# led_matrix_board.net
KiCad netlist of a schematic drawn in Altium Designer
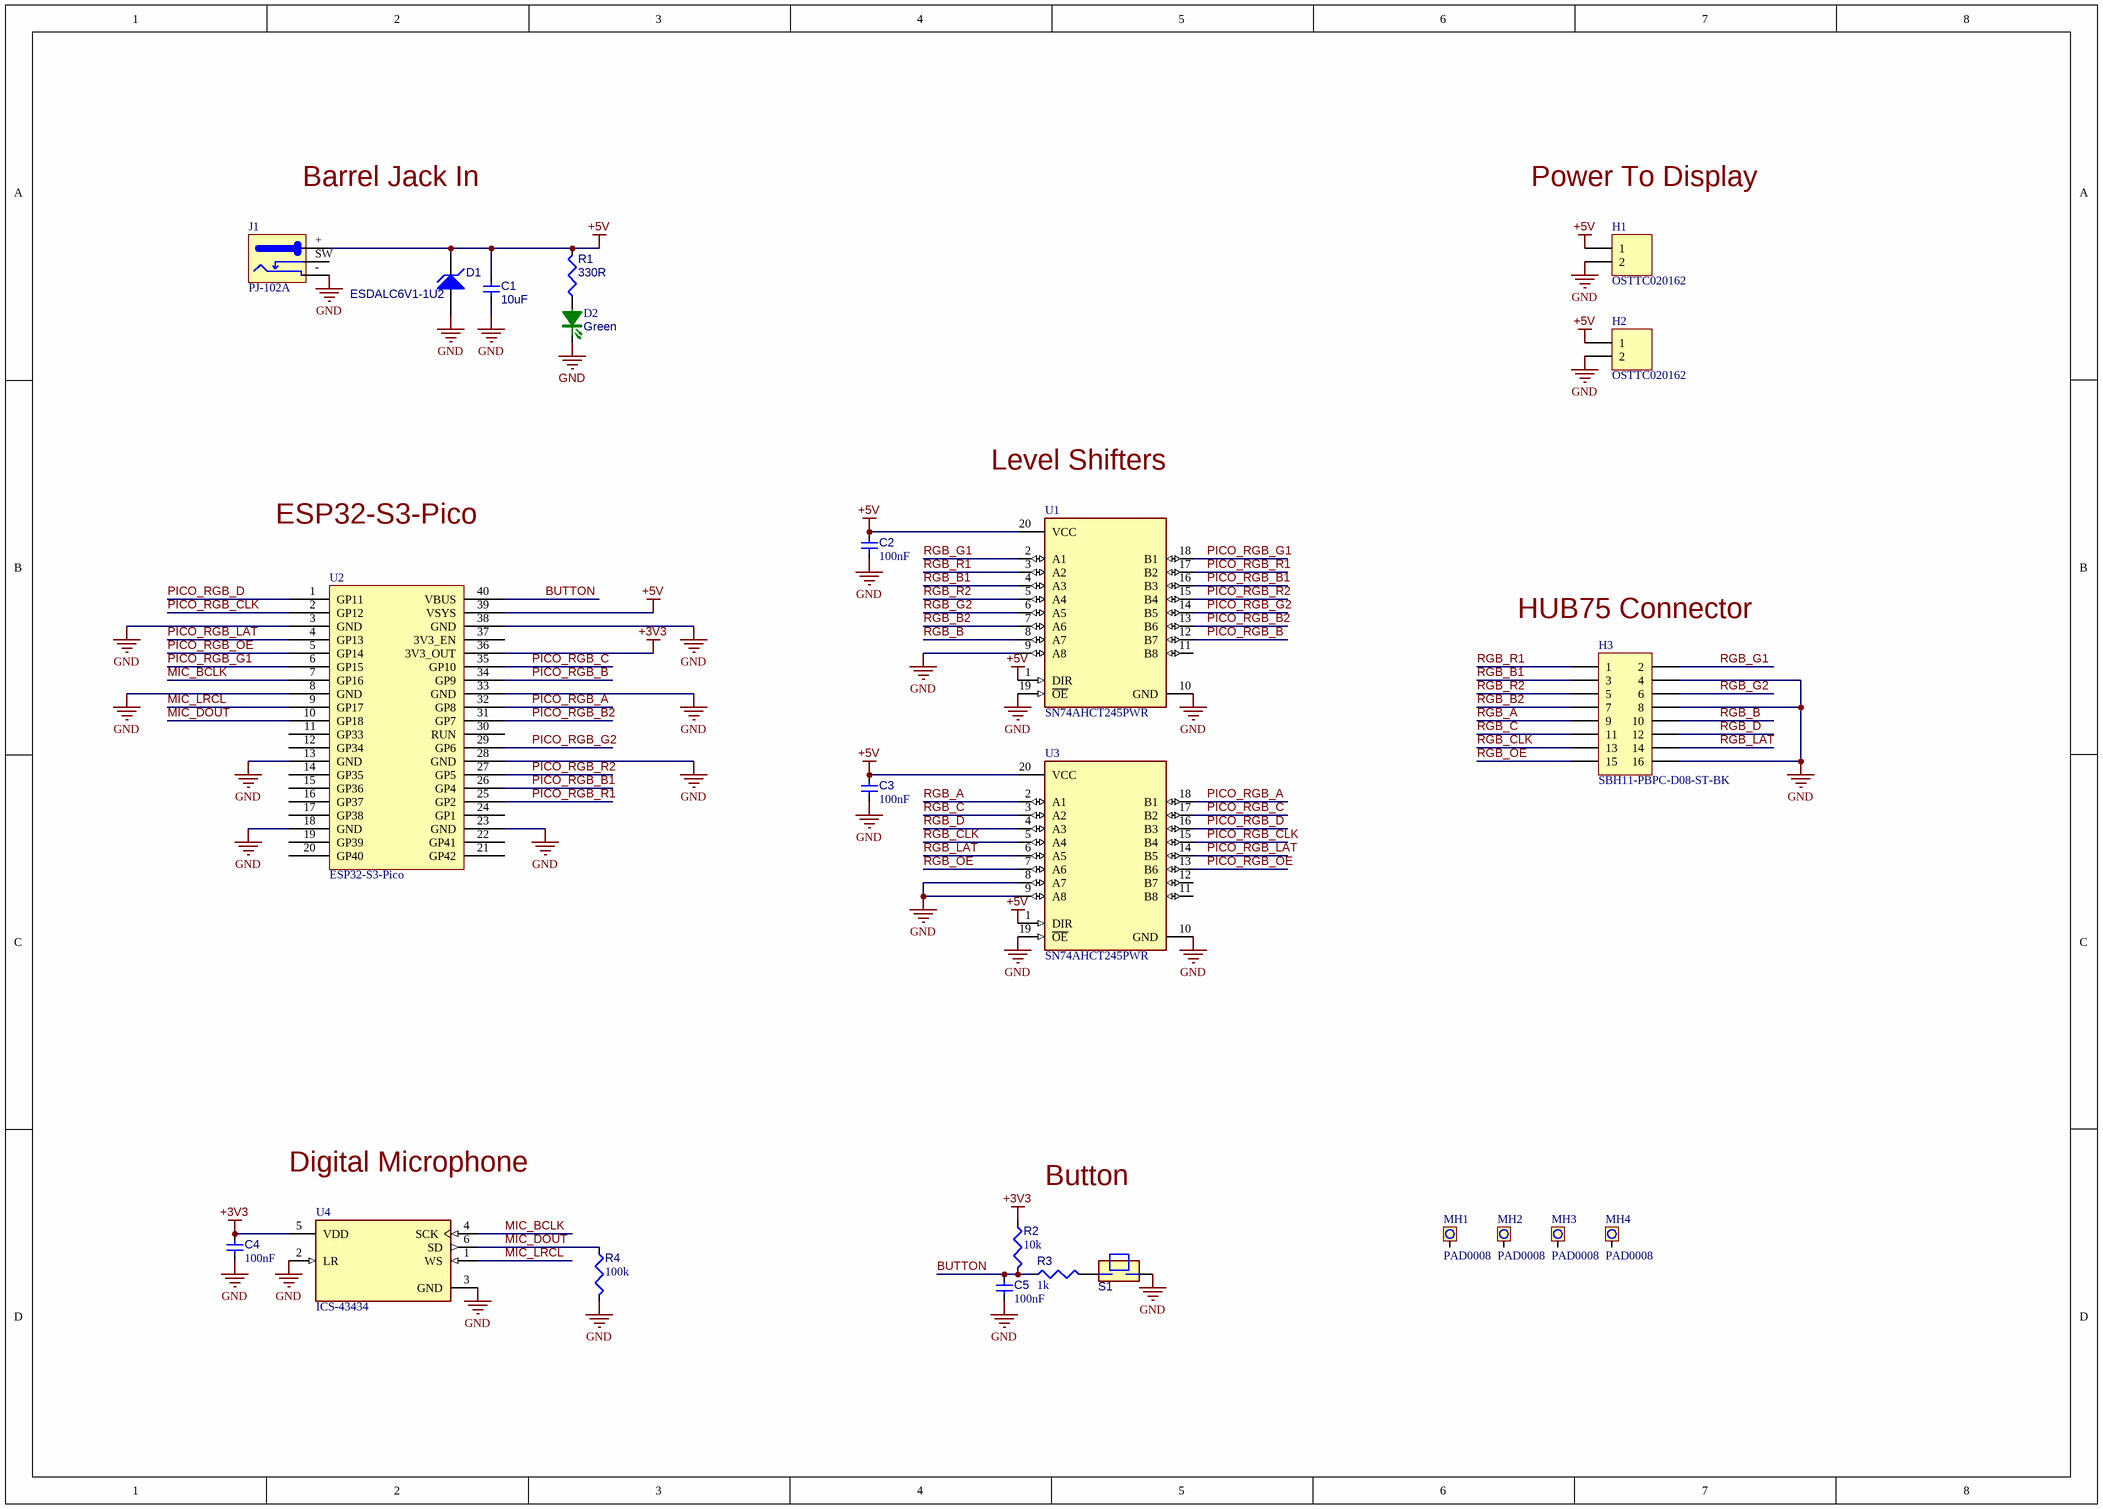
[diagram p0: led_matrix_board.SchDoc]

(export (version "E")
  (design (tool "Eeschema 10.0.6"))
  (components
    (comp (ref "C1")
      (value "10uF")
      (footprint "0603_cap_rnd")
      (description "CAP CER 10UF 25V ±20% X5R 0603")
      (fields (field (name "TOLERANCE") "20%") (field (name "VOLTAGE") "25V"))
      (libsource (lib "Morse Micro Pty Limited") (part "CAP"))
    )
    (comp (ref "C2")
      (value "100nF")
      (footprint "0603_cap")
      (description "CAP CER 100NF 10V ±10% X7R 0603")
      (fields (field (name "TOLERANCE") "10%") (field (name "VOLTAGE") "10V"))
      (libsource (lib "Morse Micro Pty Limited") (part "CAP"))
    )
    (comp (ref "C3")
      (value "100nF")
      (footprint "0603_cap")
      (description "CAP CER 100NF 10V ±10% X7R 0603")
      (fields (field (name "TOLERANCE") "10%") (field (name "VOLTAGE") "10V"))
      (libsource (lib "Morse Micro Pty Limited") (part "CAP"))
    )
    (comp (ref "C4")
      (value "100nF")
      (footprint "0603_cap")
      (description "CAP CER 100NF 10V ±10% X7R 0603")
      (fields (field (name "TOLERANCE") "10%") (field (name "VOLTAGE") "10V"))
      (libsource (lib "Morse Micro Pty Limited") (part "CAP"))
    )
    (comp (ref "C5")
      (value "100nF")
      (footprint "0603_cap")
      (description "CAP CER 100NF 10V ±10% X7R 0603")
      (fields (field (name "TOLERANCE") "10%") (field (name "VOLTAGE") "10V"))
      (libsource (lib "Morse Micro Pty Limited") (part "CAP"))
    )
    (comp (ref "D1")
      (value "ESDALC6V1-1U2")
      (footprint "0201_DIODE")
      (description "TVS DIODE 3VWM ST020")
      (fields (field (name "VOLTAGE") "3V") (field (name "POWER") "20W"))
      (libsource (lib "Morse Micro Pty Limited") (part "DIODE_ZENER"))
    )
    (comp (ref "D2")
      (value "Green")
      (footprint "LED_0402_GREEN")
      (description "LED GREEN 0402 SMD")
      (fields (field (name "VOLTAGE") "2.0V") (field (name "Comment") "XZVGR68W-3"))
      (libsource (lib "Morse Micro Pty Limited") (part "LED_G"))
    )
    (comp (ref "H1")
      (value "OSTTC020162")
      (footprint "SCREW_TERM_2WAY_5MM")
      (description "CONN TERM BLOCK 5MM 2POS")
      (libsource (lib "Morse Micro Pty Limited") (part "HDR_1X2"))
    )
    (comp (ref "H2")
      (value "OSTTC020162")
      (footprint "SCREW_TERM_2WAY_5MM")
      (description "CONN TERM BLOCK 5MM 2POS")
      (libsource (lib "Morse Micro Pty Limited") (part "HDR_1X2"))
    )
    (comp (ref "H3")
      (value "SBH11-PBPC-D08-ST-BK")
      (footprint "FP-SBH11-PBPC-D08-ST-BK-MFG")
      (description "Conn Shrouded Header (4 Sides) HDR 16 POS 2.54mm Solder ST Top Entry Thru-Hole")
      (libsource (lib "Morse Micro Pty Limited") (part "HDR_2X8"))
    )
    (comp (ref "J1")
      (value "PJ-102A")
      (footprint "PJ-102A")
      (description "Conn Power Jack 2.1mm PCB Mount Thru-Hole")
      (libsource (lib "Morse Micro Pty Limited") (part "2_1MM POWER"))
    )
    (comp (ref "MH1")
      (value "PAD0008")
      (footprint "MH_600_320_NPTH")
      (description "MH 6.00MM DIA 3.2MM HOLE NPTH")
      (libsource (lib "Morse Micro Pty Limited") (part "MH_600_320_NPTH"))
    )
    (comp (ref "MH2")
      (value "PAD0008")
      (footprint "MH_600_320_NPTH")
      (description "MH 6.00MM DIA 3.2MM HOLE NPTH")
      (libsource (lib "Morse Micro Pty Limited") (part "MH_600_320_NPTH"))
    )
    (comp (ref "MH3")
      (value "PAD0008")
      (footprint "MH_600_320_NPTH")
      (description "MH 6.00MM DIA 3.2MM HOLE NPTH")
      (libsource (lib "Morse Micro Pty Limited") (part "MH_600_320_NPTH"))
    )
    (comp (ref "MH4")
      (value "PAD0008")
      (footprint "MH_600_320_NPTH")
      (description "MH 6.00MM DIA 3.2MM HOLE NPTH")
      (libsource (lib "Morse Micro Pty Limited") (part "MH_600_320_NPTH"))
    )
    (comp (ref "R1")
      (value "330R")
      (footprint "0402_res")
      (description "RES SMD 330R OHM ±1% 1/16W 0402")
      (fields (field (name "POWER") "1/16W") (field (name "TOLERANCE") "1%"))
      (libsource (lib "Morse Micro Pty Limited") (part "RES"))
    )
    (comp (ref "R2")
      (value "10k")
      (footprint "0603_res")
      (description "RES SMD 10K OHM ±1% 1/10W 0603")
      (fields (field (name "POWER") "1/10W") (field (name "TOLERANCE") "1%"))
      (libsource (lib "Morse Micro Pty Limited") (part "RES"))
    )
    (comp (ref "R3")
      (value "1k")
      (footprint "0603_res")
      (description "RES SMD 1K OHM ±0 .1% 1/10W 0603")
      (fields (field (name "TOLERANCE") "0 .1%") (field (name "POWER") "1/10W"))
      (libsource (lib "Morse Micro Pty Limited") (part "RES"))
    )
    (comp (ref "R4")
      (value "100k")
      (footprint "0603_res")
      (description "RES SMD 100K OHM ±1% 1/10W 0603")
      (fields (field (name "POWER") "1/10W") (field (name "TOLERANCE") "1%"))
      (libsource (lib "Morse Micro Pty Limited") (part "RES"))
    )
    (comp (ref "S1")
      (value "EVQ-PF206K")
      (footprint "EVQ-PF206K")
      (description "SW, Tactile 15V@20mA, EVQ-PF, Through Hole, R/A, 7.5x7.1x5.85mm")
      (libsource (lib "Morse Micro Pty Limited") (part "SW_PB"))
    )
    (comp (ref "U1")
      (value "SN74AHCT245PWR")
      (footprint "FP-PW0020A-IPC_A")
      (description "8mA 8 4.5V~5.5V 8mA 1 TSSOP-20 Buffer/Driver/Transceiver ROHS")
      (libsource (lib "Morse Micro Pty Limited") (part "f8b0c07ade4f6b8d62f3b9458d8db27"))
    )
    (comp (ref "U2")
      (value "ESP32-S3-Pico")
      (footprint "ESP32-S3-Pico")
      (description "ESP32-S3-Pico Module.")
      (libsource (lib "Morse Micro Pty Limited") (part "ESP32-S3-Pico"))
    )
    (comp (ref "U3")
      (value "SN74AHCT245PWR")
      (footprint "FP-PW0020A-IPC_A")
      (description "8mA 8 4.5V~5.5V 8mA 1 TSSOP-20 Buffer/Driver/Transceiver ROHS")
      (libsource (lib "Morse Micro Pty Limited") (part "f8b0c07ade4f6b8d62f3b9458d8db27"))
    )
    (comp (ref "U4")
      (value "ICS-43434")
      (footprint "FP-ICS-43434-MFG")
      (description "Mic Omni-Directional -26dB 3.63V Rectangular Solder Pad T/R")
      (libsource (lib "Morse Micro Pty Limited") (part "ae05e933d23a1a1b08b70095a55dc98"))
    )
  )
  (nets
    (net (code "1") (name "+3V3") (class "Default")
      (node (ref "C4") (pin "1") (pinfunction "1_1") (pintype "passive"))
      (node (ref "R2") (pin "1") (pinfunction "1_1") (pintype "passive"))
      (node (ref "U2") (pin "36") (pinfunction "3V3_OUT_36") (pintype "passive"))
      (node (ref "U4") (pin "5") (pinfunction "VDD_5") (pintype "power_in"))
    )
    (net (code "2") (name "+5V") (class "Default")
      (node (ref "C1") (pin "1") (pinfunction "1_1") (pintype "passive"))
      (node (ref "C2") (pin "1") (pinfunction "1_1") (pintype "passive"))
      (node (ref "C3") (pin "1") (pinfunction "1_1") (pintype "passive"))
      (node (ref "D1") (pin "K") (pinfunction "K_K") (pintype "passive"))
      (node (ref "H1") (pin "1") (pinfunction "1_1") (pintype "passive"))
      (node (ref "H2") (pin "1") (pinfunction "1_1") (pintype "passive"))
      (node (ref "J1") (pin "+") (pinfunction "+_+") (pintype "passive"))
      (node (ref "R1") (pin "2") (pinfunction "2_2") (pintype "passive"))
      (node (ref "U1") (pin "1") (pinfunction "DIR_1") (pintype "input"))
      (node (ref "U1") (pin "20") (pinfunction "VCC_20") (pintype "power_in"))
      (node (ref "U2") (pin "39") (pinfunction "VSYS_39") (pintype "passive"))
      (node (ref "U3") (pin "1") (pinfunction "DIR_1") (pintype "input"))
      (node (ref "U3") (pin "20") (pinfunction "VCC_20") (pintype "power_in"))
    )
    (net (code "3") (name "/BUTTON") (class "Default")
      (node (ref "C5") (pin "1") (pinfunction "1_1") (pintype "passive"))
      (node (ref "R2") (pin "2") (pinfunction "2_2") (pintype "passive"))
      (node (ref "R3") (pin "1") (pinfunction "1_1") (pintype "passive"))
      (node (ref "U2") (pin "40") (pinfunction "VBUS_40") (pintype "passive"))
    )
    (net (code "4") (name "/MIC_BCLK") (class "Default")
      (node (ref "U2") (pin "7") (pinfunction "GP16_7") (pintype "passive"))
      (node (ref "U4") (pin "4") (pinfunction "SCK_4") (pintype "input"))
    )
    (net (code "5") (name "/MIC_DOUT") (class "Default")
      (node (ref "R4") (pin "1") (pinfunction "1_1") (pintype "passive"))
      (node (ref "U2") (pin "10") (pinfunction "GP18_10") (pintype "passive"))
      (node (ref "U4") (pin "6") (pinfunction "SD_6") (pintype "output"))
    )
    (net (code "6") (name "/MIC_LRCL") (class "Default")
      (node (ref "U2") (pin "9") (pinfunction "GP17_9") (pintype "passive"))
      (node (ref "U4") (pin "1") (pinfunction "WS_1") (pintype "input"))
    )
    (net (code "7") (name "/PICO_RGB_A") (class "Default")
      (node (ref "U2") (pin "32") (pinfunction "GP8_32") (pintype "passive"))
      (node (ref "U3") (pin "18") (pinfunction "B1_18") (pintype "bidirectional"))
    )
    (net (code "8") (name "/PICO_RGB_B") (class "Default")
      (node (ref "U1") (pin "12") (pinfunction "B7_12") (pintype "bidirectional"))
      (node (ref "U2") (pin "34") (pinfunction "GP9_34") (pintype "passive"))
    )
    (net (code "9") (name "/PICO_RGB_B1") (class "Default")
      (node (ref "U1") (pin "16") (pinfunction "B3_16") (pintype "bidirectional"))
      (node (ref "U2") (pin "26") (pinfunction "GP4_26") (pintype "passive"))
    )
    (net (code "10") (name "/PICO_RGB_B2") (class "Default")
      (node (ref "U1") (pin "13") (pinfunction "B6_13") (pintype "bidirectional"))
      (node (ref "U2") (pin "31") (pinfunction "GP7_31") (pintype "passive"))
    )
    (net (code "11") (name "/PICO_RGB_C") (class "Default")
      (node (ref "U2") (pin "35") (pinfunction "GP10_35") (pintype "passive"))
      (node (ref "U3") (pin "17") (pinfunction "B2_17") (pintype "bidirectional"))
    )
    (net (code "12") (name "/PICO_RGB_CLK") (class "Default")
      (node (ref "U2") (pin "2") (pinfunction "GP12_2") (pintype "passive"))
      (node (ref "U3") (pin "15") (pinfunction "B4_15") (pintype "bidirectional"))
    )
    (net (code "13") (name "/PICO_RGB_D") (class "Default")
      (node (ref "U2") (pin "1") (pinfunction "GP11_1") (pintype "passive"))
      (node (ref "U3") (pin "16") (pinfunction "B3_16") (pintype "bidirectional"))
    )
    (net (code "14") (name "/PICO_RGB_G1") (class "Default")
      (node (ref "U1") (pin "18") (pinfunction "B1_18") (pintype "bidirectional"))
      (node (ref "U2") (pin "6") (pinfunction "GP15_6") (pintype "passive"))
    )
    (net (code "15") (name "/PICO_RGB_G2") (class "Default")
      (node (ref "U1") (pin "14") (pinfunction "B5_14") (pintype "bidirectional"))
      (node (ref "U2") (pin "29") (pinfunction "GP6_29") (pintype "passive"))
    )
    (net (code "16") (name "/PICO_RGB_LAT") (class "Default")
      (node (ref "U2") (pin "4") (pinfunction "GP13_4") (pintype "passive"))
      (node (ref "U3") (pin "14") (pinfunction "B5_14") (pintype "bidirectional"))
    )
    (net (code "17") (name "/PICO_RGB_OE") (class "Default")
      (node (ref "U2") (pin "5") (pinfunction "GP14_5") (pintype "passive"))
      (node (ref "U3") (pin "13") (pinfunction "B6_13") (pintype "bidirectional"))
    )
    (net (code "18") (name "/PICO_RGB_R1") (class "Default")
      (node (ref "U1") (pin "17") (pinfunction "B2_17") (pintype "bidirectional"))
      (node (ref "U2") (pin "25") (pinfunction "GP2_25") (pintype "passive"))
    )
    (net (code "19") (name "/PICO_RGB_R2") (class "Default")
      (node (ref "U1") (pin "15") (pinfunction "B4_15") (pintype "bidirectional"))
      (node (ref "U2") (pin "27") (pinfunction "GP5_27") (pintype "passive"))
    )
    (net (code "20") (name "/RGB_A") (class "Default")
      (node (ref "H3") (pin "9") (pinfunction "9_9") (pintype "passive"))
      (node (ref "U3") (pin "2") (pinfunction "A1_2") (pintype "bidirectional"))
    )
    (net (code "21") (name "/RGB_B") (class "Default")
      (node (ref "H3") (pin "10") (pinfunction "10_10") (pintype "passive"))
      (node (ref "U1") (pin "8") (pinfunction "A7_8") (pintype "bidirectional"))
    )
    (net (code "22") (name "/RGB_B1") (class "Default")
      (node (ref "H3") (pin "3") (pinfunction "3_3") (pintype "passive"))
      (node (ref "U1") (pin "4") (pinfunction "A3_4") (pintype "bidirectional"))
    )
    (net (code "23") (name "/RGB_B2") (class "Default")
      (node (ref "H3") (pin "7") (pinfunction "7_7") (pintype "passive"))
      (node (ref "U1") (pin "7") (pinfunction "A6_7") (pintype "bidirectional"))
    )
    (net (code "24") (name "/RGB_C") (class "Default")
      (node (ref "H3") (pin "11") (pinfunction "11_11") (pintype "passive"))
      (node (ref "U3") (pin "3") (pinfunction "A2_3") (pintype "bidirectional"))
    )
    (net (code "25") (name "/RGB_CLK") (class "Default")
      (node (ref "H3") (pin "13") (pinfunction "13_13") (pintype "passive"))
      (node (ref "U3") (pin "5") (pinfunction "A4_5") (pintype "bidirectional"))
    )
    (net (code "26") (name "/RGB_D") (class "Default")
      (node (ref "H3") (pin "12") (pinfunction "12_12") (pintype "passive"))
      (node (ref "U3") (pin "4") (pinfunction "A3_4") (pintype "bidirectional"))
    )
    (net (code "27") (name "/RGB_G1") (class "Default")
      (node (ref "H3") (pin "2") (pinfunction "2_2") (pintype "passive"))
      (node (ref "U1") (pin "2") (pinfunction "A1_2") (pintype "bidirectional"))
    )
    (net (code "28") (name "/RGB_G2") (class "Default")
      (node (ref "H3") (pin "6") (pinfunction "6_6") (pintype "passive"))
      (node (ref "U1") (pin "6") (pinfunction "A5_6") (pintype "bidirectional"))
    )
    (net (code "29") (name "/RGB_LAT") (class "Default")
      (node (ref "H3") (pin "14") (pinfunction "14_14") (pintype "passive"))
      (node (ref "U3") (pin "6") (pinfunction "A5_6") (pintype "bidirectional"))
    )
    (net (code "30") (name "/RGB_OE") (class "Default")
      (node (ref "H3") (pin "15") (pinfunction "15_15") (pintype "passive"))
      (node (ref "U3") (pin "7") (pinfunction "A6_7") (pintype "bidirectional"))
    )
    (net (code "31") (name "/RGB_R1") (class "Default")
      (node (ref "H3") (pin "1") (pinfunction "1_1") (pintype "passive"))
      (node (ref "U1") (pin "3") (pinfunction "A2_3") (pintype "bidirectional"))
    )
    (net (code "32") (name "/RGB_R2") (class "Default")
      (node (ref "H3") (pin "5") (pinfunction "5_5") (pintype "passive"))
      (node (ref "U1") (pin "5") (pinfunction "A4_5") (pintype "bidirectional"))
    )
    (net (code "33") (name "GND") (class "Default")
      (node (ref "C1") (pin "2") (pinfunction "2_2") (pintype "passive"))
      (node (ref "C2") (pin "2") (pinfunction "2_2") (pintype "passive"))
      (node (ref "C3") (pin "2") (pinfunction "2_2") (pintype "passive"))
      (node (ref "C4") (pin "2") (pinfunction "2_2") (pintype "passive"))
      (node (ref "C5") (pin "2") (pinfunction "2_2") (pintype "passive"))
      (node (ref "D1") (pin "A") (pinfunction "A_A") (pintype "passive"))
      (node (ref "D2") (pin "K") (pinfunction "2_K") (pintype "passive"))
      (node (ref "H1") (pin "2") (pinfunction "2_2") (pintype "passive"))
      (node (ref "H2") (pin "2") (pinfunction "2_2") (pintype "passive"))
      (node (ref "H3") (pin "16") (pinfunction "16_16") (pintype "passive"))
      (node (ref "H3") (pin "4") (pinfunction "4_4") (pintype "passive"))
      (node (ref "H3") (pin "8") (pinfunction "8_8") (pintype "passive"))
      (node (ref "J1") (pin "-") (pinfunction "-_-") (pintype "passive"))
      (node (ref "R4") (pin "2") (pinfunction "2_2") (pintype "passive"))
      (node (ref "S1") (pin "2") (pinfunction "2_2") (pintype "passive"))
      (node (ref "U1") (pin "10") (pinfunction "GND_10") (pintype "power_in"))
      (node (ref "U1") (pin "19") (pinfunction "~{OE}_19") (pintype "input"))
      (node (ref "U1") (pin "9") (pinfunction "A8_9") (pintype "bidirectional"))
      (node (ref "U2") (pin "13") (pinfunction "GND_13") (pintype "passive"))
      (node (ref "U2") (pin "18") (pinfunction "GND_18") (pintype "passive"))
      (node (ref "U2") (pin "23") (pinfunction "GND_23") (pintype "passive"))
      (node (ref "U2") (pin "28") (pinfunction "GND_28") (pintype "passive"))
      (node (ref "U2") (pin "3") (pinfunction "GND_3") (pintype "passive"))
      (node (ref "U2") (pin "33") (pinfunction "GND_33") (pintype "passive"))
      (node (ref "U2") (pin "38") (pinfunction "GND_38") (pintype "passive"))
      (node (ref "U2") (pin "8") (pinfunction "GND_8") (pintype "passive"))
      (node (ref "U3") (pin "10") (pinfunction "GND_10") (pintype "power_in"))
      (node (ref "U3") (pin "19") (pinfunction "~{OE}_19") (pintype "input"))
      (node (ref "U3") (pin "8") (pinfunction "A7_8") (pintype "bidirectional"))
      (node (ref "U3") (pin "9") (pinfunction "A8_9") (pintype "bidirectional"))
      (node (ref "U4") (pin "2") (pinfunction "LR_2") (pintype "input"))
      (node (ref "U4") (pin "3") (pinfunction "GND_3") (pintype "power_in"))
    )
    (net (code "34") (name "Net-(D2-1)") (class "Default")
      (node (ref "D2") (pin "A") (pinfunction "1_A") (pintype "passive"))
      (node (ref "R1") (pin "1") (pinfunction "1_1") (pintype "passive"))
    )
    (net (code "35") (name "Net-(R3-Pad2)") (class "Default")
      (node (ref "R3") (pin "2") (pinfunction "2_2") (pintype "passive"))
      (node (ref "S1") (pin "1") (pinfunction "1_1") (pintype "passive"))
    )
    (net (code "36") (name "unconnected-(J1-PadSW)") (class "Default")
      (node (ref "J1") (pin "SW") (pinfunction "SW_SW") (pintype "passive"))
    )
    (net (code "37") (name "unconnected-(MH1-Pad1)") (class "Default")
      (node (ref "MH1") (pin "1") (pinfunction "1_1") (pintype "passive"))
    )
    (net (code "38") (name "unconnected-(MH2-Pad1)") (class "Default")
      (node (ref "MH2") (pin "1") (pinfunction "1_1") (pintype "passive"))
    )
    (net (code "39") (name "unconnected-(MH3-Pad1)") (class "Default")
      (node (ref "MH3") (pin "1") (pinfunction "1_1") (pintype "passive"))
    )
    (net (code "40") (name "unconnected-(MH4-Pad1)") (class "Default")
      (node (ref "MH4") (pin "1") (pinfunction "1_1") (pintype "passive"))
    )
    (net (code "41") (name "unconnected-(U1-B8-Pad11)") (class "Default")
      (node (ref "U1") (pin "11") (pinfunction "B8_11") (pintype "bidirectional"))
    )
    (net (code "42") (name "unconnected-(U2-3V3_EN-Pad37)") (class "Default")
      (node (ref "U2") (pin "37") (pinfunction "3V3_EN_37") (pintype "passive"))
    )
    (net (code "43") (name "unconnected-(U2-GP1-Pad24)") (class "Default")
      (node (ref "U2") (pin "24") (pinfunction "GP1_24") (pintype "passive"))
    )
    (net (code "44") (name "unconnected-(U2-GP33-Pad11)") (class "Default")
      (node (ref "U2") (pin "11") (pinfunction "GP33_11") (pintype "passive"))
    )
    (net (code "45") (name "unconnected-(U2-GP34-Pad12)") (class "Default")
      (node (ref "U2") (pin "12") (pinfunction "GP34_12") (pintype "passive"))
    )
    (net (code "46") (name "unconnected-(U2-GP35-Pad14)") (class "Default")
      (node (ref "U2") (pin "14") (pinfunction "GP35_14") (pintype "passive"))
    )
    (net (code "47") (name "unconnected-(U2-GP36-Pad15)") (class "Default")
      (node (ref "U2") (pin "15") (pinfunction "GP36_15") (pintype "passive"))
    )
    (net (code "48") (name "unconnected-(U2-GP37-Pad16)") (class "Default")
      (node (ref "U2") (pin "16") (pinfunction "GP37_16") (pintype "passive"))
    )
    (net (code "49") (name "unconnected-(U2-GP38-Pad17)") (class "Default")
      (node (ref "U2") (pin "17") (pinfunction "GP38_17") (pintype "passive"))
    )
    (net (code "50") (name "unconnected-(U2-GP39-Pad19)") (class "Default")
      (node (ref "U2") (pin "19") (pinfunction "GP39_19") (pintype "passive"))
    )
    (net (code "51") (name "unconnected-(U2-GP40-Pad20)") (class "Default")
      (node (ref "U2") (pin "20") (pinfunction "GP40_20") (pintype "passive"))
    )
    (net (code "52") (name "unconnected-(U2-GP41-Pad22)") (class "Default")
      (node (ref "U2") (pin "22") (pinfunction "GP41_22") (pintype "passive"))
    )
    (net (code "53") (name "unconnected-(U2-GP42-Pad21)") (class "Default")
      (node (ref "U2") (pin "21") (pinfunction "GP42_21") (pintype "passive"))
    )
    (net (code "54") (name "unconnected-(U2-RUN-Pad30)") (class "Default")
      (node (ref "U2") (pin "30") (pinfunction "RUN_30") (pintype "passive"))
    )
    (net (code "55") (name "unconnected-(U3-B7-Pad12)") (class "Default")
      (node (ref "U3") (pin "12") (pinfunction "B7_12") (pintype "bidirectional"))
    )
    (net (code "56") (name "unconnected-(U3-B8-Pad11)") (class "Default")
      (node (ref "U3") (pin "11") (pinfunction "B8_11") (pintype "bidirectional"))
    )
  )
)
